# Sensors.net
KiCad netlist of a schematic drawn in EAGLE
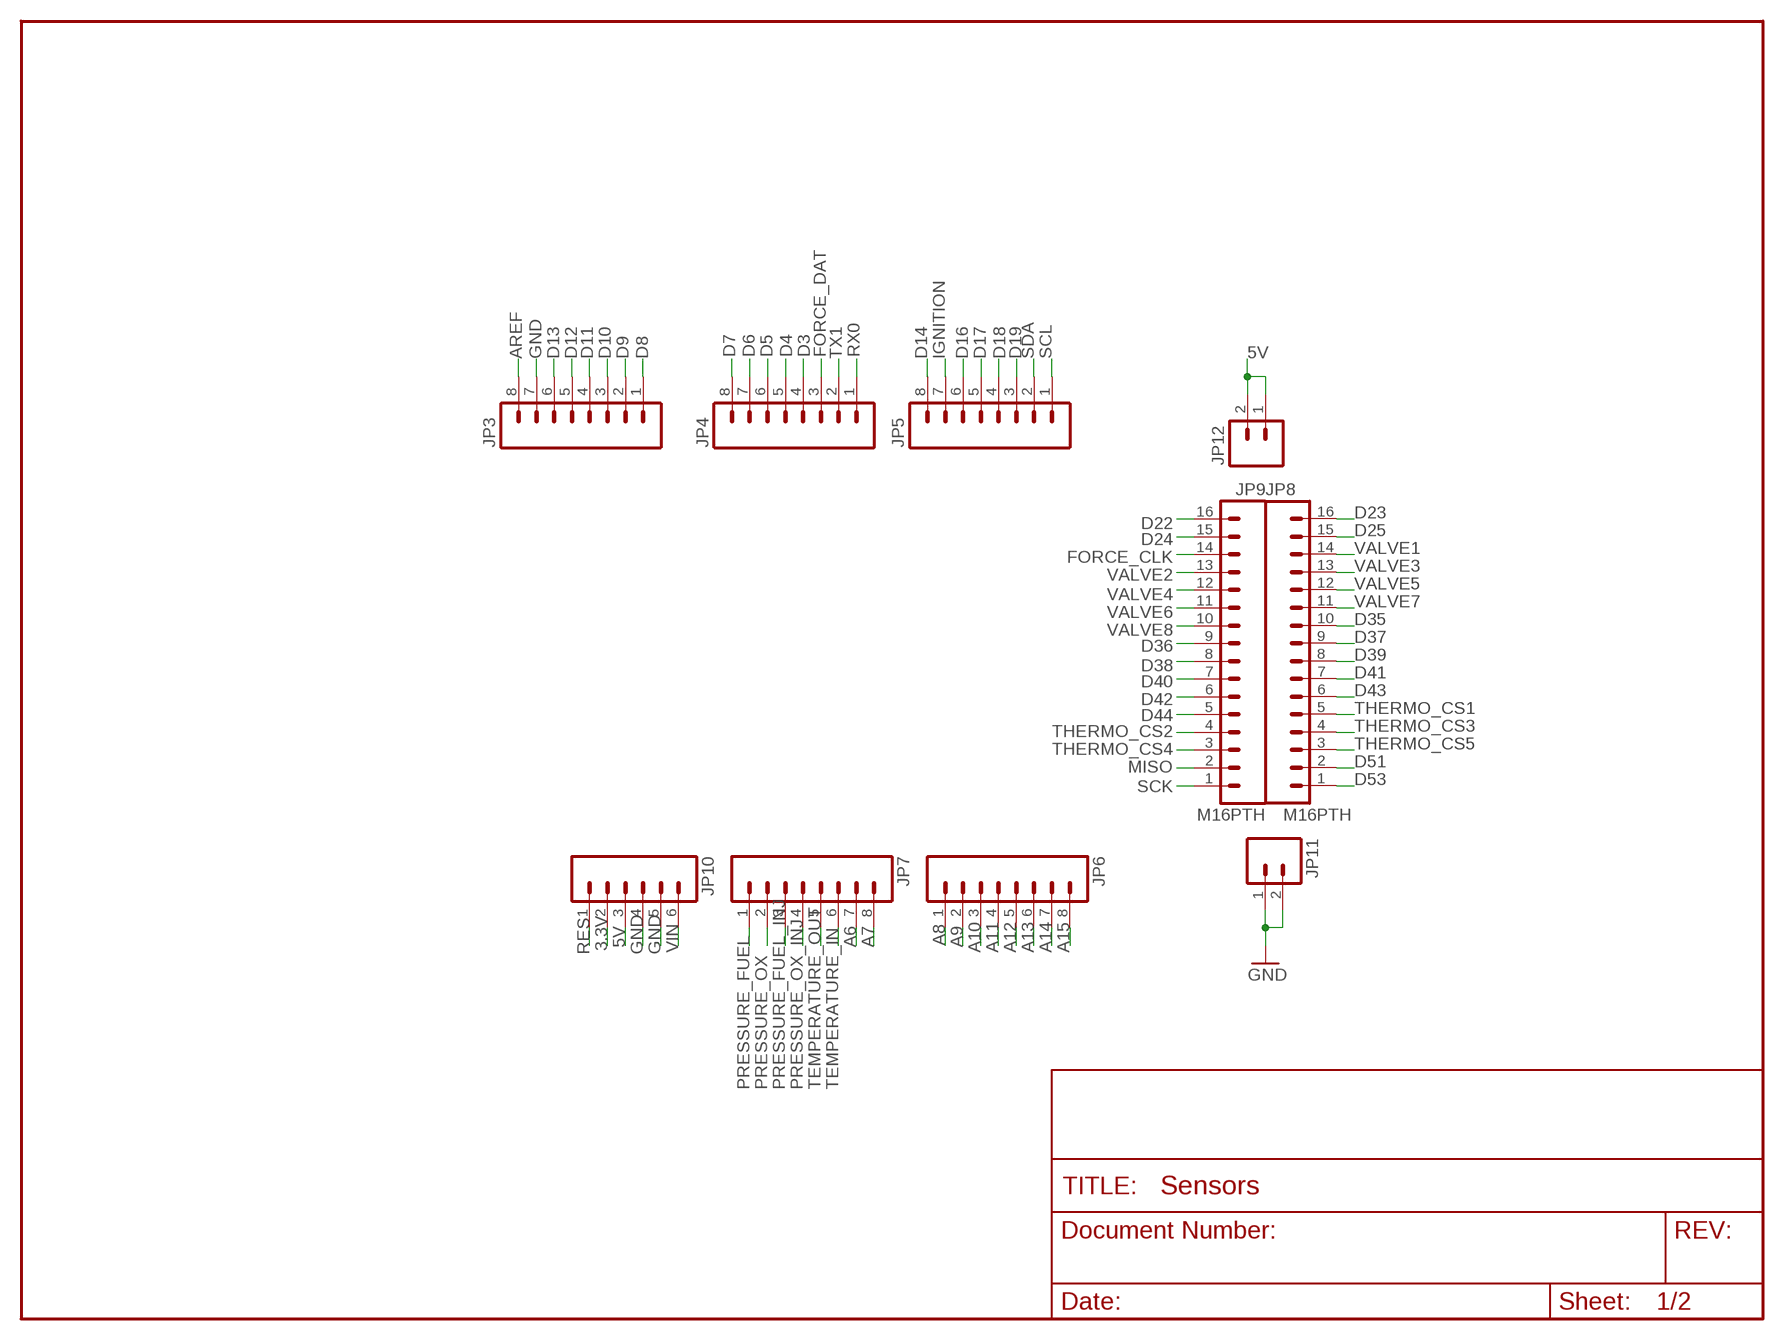
[diagram p0: schematic, sheet 1]
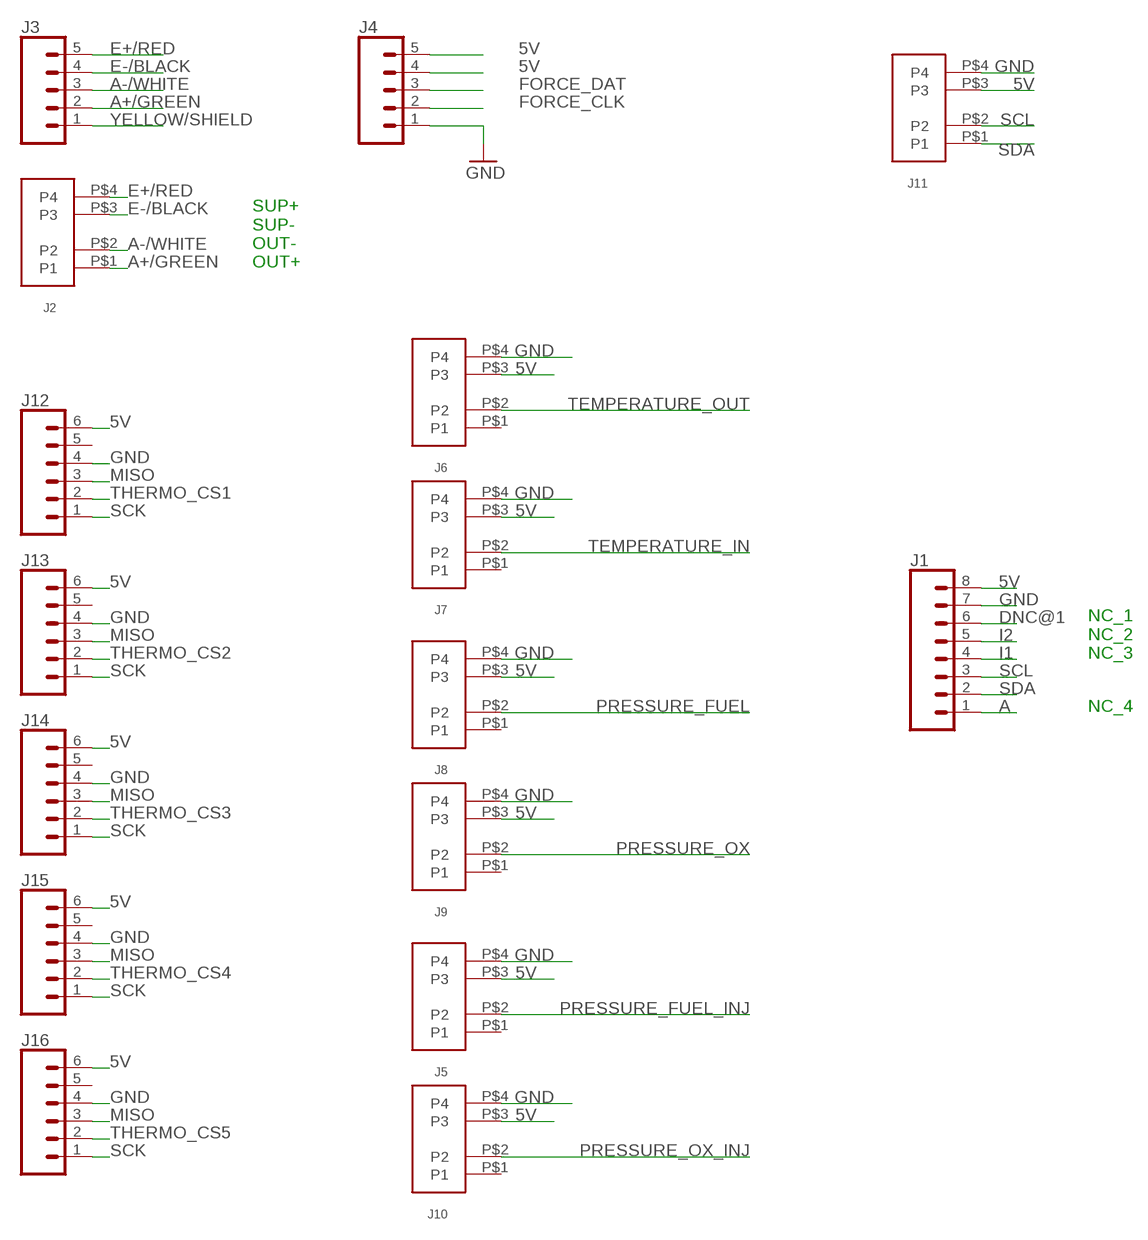
[diagram p1: schematic, sheet 2]

(export (version "E")
  (design (tool "Eeschema 10.0.6"))
  (components
    (comp (ref "J1")
      (value "CONN_08\"")
      (footprint "eagle-import:1X08")
      (libsource (lib "eagle-import") (part "CONN_08{dblquote}"))
    )
    (comp (ref "J2")
      (value "JST_CONNECTOR")
      (footprint "eagle-import:B4B-XH-A(LF)(SN)")
      (libsource (lib "eagle-import") (part "JST_CONNECTOR"))
    )
    (comp (ref "J3")
      (value "CONN_05")
      (footprint "eagle-import:1X05")
      (libsource (lib "eagle-import") (part "CONN_05"))
    )
    (comp (ref "J4")
      (value "CONN_05")
      (footprint "eagle-import:1X05")
      (libsource (lib "eagle-import") (part "CONN_05"))
    )
    (comp (ref "J5")
      (value "JST_CONNECTOR")
      (footprint "eagle-import:B4B-XH-A(LF)(SN)")
      (libsource (lib "eagle-import") (part "JST_CONNECTOR"))
    )
    (comp (ref "J6")
      (value "JST_CONNECTOR")
      (footprint "eagle-import:B4B-XH-A(LF)(SN)")
      (libsource (lib "eagle-import") (part "JST_CONNECTOR"))
    )
    (comp (ref "J7")
      (value "JST_CONNECTOR")
      (footprint "eagle-import:B4B-XH-A(LF)(SN)")
      (libsource (lib "eagle-import") (part "JST_CONNECTOR"))
    )
    (comp (ref "J8")
      (value "JST_CONNECTOR")
      (footprint "eagle-import:B4B-XH-A(LF)(SN)")
      (libsource (lib "eagle-import") (part "JST_CONNECTOR"))
    )
    (comp (ref "J9")
      (value "JST_CONNECTOR")
      (footprint "eagle-import:B4B-XH-A(LF)(SN)")
      (libsource (lib "eagle-import") (part "JST_CONNECTOR"))
    )
    (comp (ref "J10")
      (value "JST_CONNECTOR")
      (footprint "eagle-import:B4B-XH-A(LF)(SN)")
      (libsource (lib "eagle-import") (part "JST_CONNECTOR"))
    )
    (comp (ref "J11")
      (value "JST_CONNECTOR")
      (footprint "eagle-import:B4B-XH-A(LF)(SN)")
      (libsource (lib "eagle-import") (part "JST_CONNECTOR"))
    )
    (comp (ref "J12")
      (value "CONN_06SILK_FEMALE_PTH")
      (footprint "eagle-import:1X06")
      (libsource (lib "eagle-import") (part "CONN_06SILK_FEMALE_PTH"))
    )
    (comp (ref "J13")
      (value "CONN_06SILK_FEMALE_PTH")
      (footprint "eagle-import:1X06")
      (libsource (lib "eagle-import") (part "CONN_06SILK_FEMALE_PTH"))
    )
    (comp (ref "J14")
      (value "CONN_06SILK_FEMALE_PTH")
      (footprint "eagle-import:1X06")
      (libsource (lib "eagle-import") (part "CONN_06SILK_FEMALE_PTH"))
    )
    (comp (ref "J15")
      (value "CONN_06SILK_FEMALE_PTH")
      (footprint "eagle-import:1X06")
      (libsource (lib "eagle-import") (part "CONN_06SILK_FEMALE_PTH"))
    )
    (comp (ref "J16")
      (value "CONN_06SILK_FEMALE_PTH")
      (footprint "eagle-import:1X06")
      (libsource (lib "eagle-import") (part "CONN_06SILK_FEMALE_PTH"))
    )
    (comp (ref "JP3")
      (value "M08")
      (footprint "eagle-import:1X08")
      (libsource (lib "eagle-import") (part "M08"))
    )
    (comp (ref "JP4")
      (value "M08")
      (footprint "eagle-import:1X08")
      (libsource (lib "eagle-import") (part "M08"))
    )
    (comp (ref "JP5")
      (value "M08")
      (footprint "eagle-import:1X08")
      (libsource (lib "eagle-import") (part "M08"))
    )
    (comp (ref "JP6")
      (value "M08")
      (footprint "eagle-import:1X08")
      (libsource (lib "eagle-import") (part "M08"))
    )
    (comp (ref "JP7")
      (value "M08")
      (footprint "eagle-import:1X08")
      (libsource (lib "eagle-import") (part "M08"))
    )
    (comp (ref "JP8")
      (value "M16PTH")
      (footprint "eagle-import:1X16")
      (libsource (lib "eagle-import") (part "M16PTH"))
    )
    (comp (ref "JP9")
      (value "M16PTH")
      (footprint "eagle-import:1X16")
      (libsource (lib "eagle-import") (part "M16PTH"))
    )
    (comp (ref "JP10")
      (value "M06SIP")
      (footprint "eagle-import:1X06")
      (libsource (lib "eagle-import") (part "M06SIP"))
    )
    (comp (ref "JP11")
      (value "M02PTH")
      (footprint "eagle-import:1X02")
      (libsource (lib "eagle-import") (part "M02PTH"))
    )
    (comp (ref "JP12")
      (value "M02PTH")
      (footprint "eagle-import:1X02")
      (libsource (lib "eagle-import") (part "M02PTH"))
    )
  )
  (nets
    (net (code "1") (name "3.3V") (class "Default")
      (node (ref "JP10") (pin "2") (pinfunction "2_2") (pintype "passive"))
    )
    (net (code "2") (name "5V") (class "Default")
      (node (ref "J1") (pin "8") (pinfunction "8_8") (pintype "passive"))
      (node (ref "J10") (pin "P$3") (pinfunction "P3_P$3") (pintype "bidirectional"))
      (node (ref "J11") (pin "P$3") (pinfunction "P3_P$3") (pintype "bidirectional"))
      (node (ref "J12") (pin "6") (pinfunction "6_6") (pintype "passive"))
      (node (ref "J13") (pin "6") (pinfunction "6_6") (pintype "passive"))
      (node (ref "J14") (pin "6") (pinfunction "6_6") (pintype "passive"))
      (node (ref "J15") (pin "6") (pinfunction "6_6") (pintype "passive"))
      (node (ref "J16") (pin "6") (pinfunction "6_6") (pintype "passive"))
      (node (ref "J4") (pin "4") (pinfunction "4_4") (pintype "passive"))
      (node (ref "J4") (pin "5") (pinfunction "5_5") (pintype "passive"))
      (node (ref "J5") (pin "P$3") (pinfunction "P3_P$3") (pintype "bidirectional"))
      (node (ref "J6") (pin "P$3") (pinfunction "P3_P$3") (pintype "bidirectional"))
      (node (ref "J7") (pin "P$3") (pinfunction "P3_P$3") (pintype "bidirectional"))
      (node (ref "J8") (pin "P$3") (pinfunction "P3_P$3") (pintype "bidirectional"))
      (node (ref "J9") (pin "P$3") (pinfunction "P3_P$3") (pintype "bidirectional"))
      (node (ref "JP10") (pin "3") (pinfunction "3_3") (pintype "passive"))
      (node (ref "JP12") (pin "1") (pinfunction "1_1") (pintype "passive"))
      (node (ref "JP12") (pin "2") (pinfunction "2_2") (pintype "passive"))
    )
    (net (code "3") (name "A") (class "Default")
      (node (ref "J1") (pin "1") (pinfunction "1_1") (pintype "passive"))
    )
    (net (code "4") (name "A+{slash}GREEN") (class "Default")
      (node (ref "J2") (pin "P$1") (pinfunction "P1_P$1") (pintype "bidirectional"))
      (node (ref "J3") (pin "2") (pinfunction "2_2") (pintype "passive"))
    )
    (net (code "5") (name "A-{slash}WHITE") (class "Default")
      (node (ref "J2") (pin "P$2") (pinfunction "P2_P$2") (pintype "bidirectional"))
      (node (ref "J3") (pin "3") (pinfunction "3_3") (pintype "passive"))
    )
    (net (code "6") (name "A6") (class "Default")
      (node (ref "JP7") (pin "7") (pinfunction "7_7") (pintype "passive"))
    )
    (net (code "7") (name "A7") (class "Default")
      (node (ref "JP7") (pin "8") (pinfunction "8_8") (pintype "passive"))
    )
    (net (code "8") (name "A8") (class "Default")
      (node (ref "JP6") (pin "1") (pinfunction "1_1") (pintype "passive"))
    )
    (net (code "9") (name "A9") (class "Default")
      (node (ref "JP6") (pin "2") (pinfunction "2_2") (pintype "passive"))
    )
    (net (code "10") (name "A10") (class "Default")
      (node (ref "JP6") (pin "3") (pinfunction "3_3") (pintype "passive"))
    )
    (net (code "11") (name "A11") (class "Default")
      (node (ref "JP6") (pin "4") (pinfunction "4_4") (pintype "passive"))
    )
    (net (code "12") (name "A12") (class "Default")
      (node (ref "JP6") (pin "5") (pinfunction "5_5") (pintype "passive"))
    )
    (net (code "13") (name "A13") (class "Default")
      (node (ref "JP6") (pin "6") (pinfunction "6_6") (pintype "passive"))
    )
    (net (code "14") (name "A14") (class "Default")
      (node (ref "JP6") (pin "7") (pinfunction "7_7") (pintype "passive"))
    )
    (net (code "15") (name "A15") (class "Default")
      (node (ref "JP6") (pin "8") (pinfunction "8_8") (pintype "passive"))
    )
    (net (code "16") (name "AREF") (class "Default")
      (node (ref "JP3") (pin "8") (pinfunction "8_8") (pintype "passive"))
    )
    (net (code "17") (name "D3") (class "Default")
      (node (ref "JP4") (pin "4") (pinfunction "4_4") (pintype "passive"))
    )
    (net (code "18") (name "D4") (class "Default")
      (node (ref "JP4") (pin "5") (pinfunction "5_5") (pintype "passive"))
    )
    (net (code "19") (name "D5") (class "Default")
      (node (ref "JP4") (pin "6") (pinfunction "6_6") (pintype "passive"))
    )
    (net (code "20") (name "D6") (class "Default")
      (node (ref "JP4") (pin "7") (pinfunction "7_7") (pintype "passive"))
    )
    (net (code "21") (name "D7") (class "Default")
      (node (ref "JP4") (pin "8") (pinfunction "8_8") (pintype "passive"))
    )
    (net (code "22") (name "D8") (class "Default")
      (node (ref "JP3") (pin "1") (pinfunction "1_1") (pintype "passive"))
    )
    (net (code "23") (name "D9") (class "Default")
      (node (ref "JP3") (pin "2") (pinfunction "2_2") (pintype "passive"))
    )
    (net (code "24") (name "D10") (class "Default")
      (node (ref "JP3") (pin "3") (pinfunction "3_3") (pintype "passive"))
    )
    (net (code "25") (name "D11") (class "Default")
      (node (ref "JP3") (pin "4") (pinfunction "4_4") (pintype "passive"))
    )
    (net (code "26") (name "D12") (class "Default")
      (node (ref "JP3") (pin "5") (pinfunction "5_5") (pintype "passive"))
    )
    (net (code "27") (name "D13") (class "Default")
      (node (ref "JP3") (pin "6") (pinfunction "6_6") (pintype "passive"))
    )
    (net (code "28") (name "D14") (class "Default")
      (node (ref "JP5") (pin "8") (pinfunction "8_8") (pintype "passive"))
    )
    (net (code "29") (name "D16") (class "Default")
      (node (ref "JP5") (pin "6") (pinfunction "6_6") (pintype "passive"))
    )
    (net (code "30") (name "D17") (class "Default")
      (node (ref "JP5") (pin "5") (pinfunction "5_5") (pintype "passive"))
    )
    (net (code "31") (name "D18") (class "Default")
      (node (ref "JP5") (pin "4") (pinfunction "4_4") (pintype "passive"))
    )
    (net (code "32") (name "D19") (class "Default")
      (node (ref "JP5") (pin "3") (pinfunction "3_3") (pintype "passive"))
    )
    (net (code "33") (name "D22") (class "Default")
      (node (ref "JP9") (pin "16") (pinfunction "16_16") (pintype "passive"))
    )
    (net (code "34") (name "D23") (class "Default")
      (node (ref "JP8") (pin "16") (pinfunction "16_16") (pintype "passive"))
    )
    (net (code "35") (name "D24") (class "Default")
      (node (ref "JP9") (pin "15") (pinfunction "15_15") (pintype "passive"))
    )
    (net (code "36") (name "D25") (class "Default")
      (node (ref "JP8") (pin "15") (pinfunction "15_15") (pintype "passive"))
    )
    (net (code "37") (name "D35") (class "Default")
      (node (ref "JP8") (pin "10") (pinfunction "10_10") (pintype "passive"))
    )
    (net (code "38") (name "D36") (class "Default")
      (node (ref "JP9") (pin "9") (pinfunction "9_9") (pintype "passive"))
    )
    (net (code "39") (name "D37") (class "Default")
      (node (ref "JP8") (pin "9") (pinfunction "9_9") (pintype "passive"))
    )
    (net (code "40") (name "D38") (class "Default")
      (node (ref "JP9") (pin "8") (pinfunction "8_8") (pintype "passive"))
    )
    (net (code "41") (name "D39") (class "Default")
      (node (ref "JP8") (pin "8") (pinfunction "8_8") (pintype "passive"))
    )
    (net (code "42") (name "D40") (class "Default")
      (node (ref "JP9") (pin "7") (pinfunction "7_7") (pintype "passive"))
    )
    (net (code "43") (name "D41") (class "Default")
      (node (ref "JP8") (pin "7") (pinfunction "7_7") (pintype "passive"))
    )
    (net (code "44") (name "D42") (class "Default")
      (node (ref "JP9") (pin "6") (pinfunction "6_6") (pintype "passive"))
    )
    (net (code "45") (name "D43") (class "Default")
      (node (ref "JP8") (pin "6") (pinfunction "6_6") (pintype "passive"))
    )
    (net (code "46") (name "D44") (class "Default")
      (node (ref "JP9") (pin "5") (pinfunction "5_5") (pintype "passive"))
    )
    (net (code "47") (name "D51") (class "Default")
      (node (ref "JP8") (pin "2") (pinfunction "2_2") (pintype "passive"))
    )
    (net (code "48") (name "D53") (class "Default")
      (node (ref "JP8") (pin "1") (pinfunction "1_1") (pintype "passive"))
    )
    (net (code "49") (name "DNC@1") (class "Default")
      (node (ref "J1") (pin "6") (pinfunction "6_6") (pintype "passive"))
    )
    (net (code "50") (name "E+{slash}RED") (class "Default")
      (node (ref "J2") (pin "P$4") (pinfunction "P4_P$4") (pintype "bidirectional"))
      (node (ref "J3") (pin "5") (pinfunction "5_5") (pintype "passive"))
    )
    (net (code "51") (name "E-{slash}BLACK") (class "Default")
      (node (ref "J2") (pin "P$3") (pinfunction "P3_P$3") (pintype "bidirectional"))
      (node (ref "J3") (pin "4") (pinfunction "4_4") (pintype "passive"))
    )
    (net (code "52") (name "FORCE_CLK") (class "Default")
      (node (ref "J4") (pin "2") (pinfunction "2_2") (pintype "passive"))
      (node (ref "JP9") (pin "14") (pinfunction "14_14") (pintype "passive"))
    )
    (net (code "53") (name "FORCE_DAT") (class "Default")
      (node (ref "J4") (pin "3") (pinfunction "3_3") (pintype "passive"))
      (node (ref "JP4") (pin "3") (pinfunction "3_3") (pintype "passive"))
    )
    (net (code "54") (name "GND") (class "Default")
      (node (ref "J1") (pin "7") (pinfunction "7_7") (pintype "passive"))
      (node (ref "J10") (pin "P$4") (pinfunction "P4_P$4") (pintype "bidirectional"))
      (node (ref "J11") (pin "P$4") (pinfunction "P4_P$4") (pintype "bidirectional"))
      (node (ref "J12") (pin "4") (pinfunction "4_4") (pintype "passive"))
      (node (ref "J13") (pin "4") (pinfunction "4_4") (pintype "passive"))
      (node (ref "J14") (pin "4") (pinfunction "4_4") (pintype "passive"))
      (node (ref "J15") (pin "4") (pinfunction "4_4") (pintype "passive"))
      (node (ref "J16") (pin "4") (pinfunction "4_4") (pintype "passive"))
      (node (ref "J4") (pin "1") (pinfunction "1_1") (pintype "passive"))
      (node (ref "J5") (pin "P$4") (pinfunction "P4_P$4") (pintype "bidirectional"))
      (node (ref "J6") (pin "P$4") (pinfunction "P4_P$4") (pintype "bidirectional"))
      (node (ref "J7") (pin "P$4") (pinfunction "P4_P$4") (pintype "bidirectional"))
      (node (ref "J8") (pin "P$4") (pinfunction "P4_P$4") (pintype "bidirectional"))
      (node (ref "J9") (pin "P$4") (pinfunction "P4_P$4") (pintype "bidirectional"))
      (node (ref "JP10") (pin "4") (pinfunction "4_4") (pintype "passive"))
      (node (ref "JP10") (pin "5") (pinfunction "5_5") (pintype "passive"))
      (node (ref "JP11") (pin "1") (pinfunction "1_1") (pintype "passive"))
      (node (ref "JP11") (pin "2") (pinfunction "2_2") (pintype "passive"))
      (node (ref "JP3") (pin "7") (pinfunction "7_7") (pintype "passive"))
    )
    (net (code "55") (name "I1") (class "Default")
      (node (ref "J1") (pin "4") (pinfunction "4_4") (pintype "passive"))
    )
    (net (code "56") (name "I2") (class "Default")
      (node (ref "J1") (pin "5") (pinfunction "5_5") (pintype "passive"))
    )
    (net (code "57") (name "IGNITION") (class "Default")
      (node (ref "JP5") (pin "7") (pinfunction "7_7") (pintype "passive"))
    )
    (net (code "58") (name "MISO") (class "Default")
      (node (ref "J12") (pin "3") (pinfunction "3_3") (pintype "passive"))
      (node (ref "J13") (pin "3") (pinfunction "3_3") (pintype "passive"))
      (node (ref "J14") (pin "3") (pinfunction "3_3") (pintype "passive"))
      (node (ref "J15") (pin "3") (pinfunction "3_3") (pintype "passive"))
      (node (ref "J16") (pin "3") (pinfunction "3_3") (pintype "passive"))
      (node (ref "JP9") (pin "2") (pinfunction "2_2") (pintype "passive"))
    )
    (net (code "59") (name "PRESSURE_FUEL") (class "Default")
      (node (ref "J8") (pin "P$2") (pinfunction "P2_P$2") (pintype "bidirectional"))
      (node (ref "JP7") (pin "1") (pinfunction "1_1") (pintype "passive"))
    )
    (net (code "60") (name "PRESSURE_FUEL_INJ") (class "Default")
      (node (ref "J5") (pin "P$2") (pinfunction "P2_P$2") (pintype "bidirectional"))
      (node (ref "JP7") (pin "3") (pinfunction "3_3") (pintype "passive"))
    )
    (net (code "61") (name "PRESSURE_OX") (class "Default")
      (node (ref "J9") (pin "P$2") (pinfunction "P2_P$2") (pintype "bidirectional"))
      (node (ref "JP7") (pin "2") (pinfunction "2_2") (pintype "passive"))
    )
    (net (code "62") (name "PRESSURE_OX_INJ") (class "Default")
      (node (ref "J10") (pin "P$2") (pinfunction "P2_P$2") (pintype "bidirectional"))
      (node (ref "JP7") (pin "4") (pinfunction "4_4") (pintype "passive"))
    )
    (net (code "63") (name "RES") (class "Default")
      (node (ref "JP10") (pin "1") (pinfunction "1_1") (pintype "passive"))
    )
    (net (code "64") (name "RX0") (class "Default")
      (node (ref "JP4") (pin "1") (pinfunction "1_1") (pintype "passive"))
    )
    (net (code "65") (name "SCK") (class "Default")
      (node (ref "J12") (pin "1") (pinfunction "1_1") (pintype "passive"))
      (node (ref "J13") (pin "1") (pinfunction "1_1") (pintype "passive"))
      (node (ref "J14") (pin "1") (pinfunction "1_1") (pintype "passive"))
      (node (ref "J15") (pin "1") (pinfunction "1_1") (pintype "passive"))
      (node (ref "J16") (pin "1") (pinfunction "1_1") (pintype "passive"))
      (node (ref "JP9") (pin "1") (pinfunction "1_1") (pintype "passive"))
    )
    (net (code "66") (name "SCL") (class "Default")
      (node (ref "J1") (pin "3") (pinfunction "3_3") (pintype "passive"))
      (node (ref "J11") (pin "P$2") (pinfunction "P2_P$2") (pintype "bidirectional"))
      (node (ref "JP5") (pin "1") (pinfunction "1_1") (pintype "passive"))
    )
    (net (code "67") (name "SDA") (class "Default")
      (node (ref "J1") (pin "2") (pinfunction "2_2") (pintype "passive"))
      (node (ref "J11") (pin "P$1") (pinfunction "P1_P$1") (pintype "bidirectional"))
      (node (ref "JP5") (pin "2") (pinfunction "2_2") (pintype "passive"))
    )
    (net (code "68") (name "TEMPERATURE_IN") (class "Default")
      (node (ref "J7") (pin "P$2") (pinfunction "P2_P$2") (pintype "bidirectional"))
      (node (ref "JP7") (pin "6") (pinfunction "6_6") (pintype "passive"))
    )
    (net (code "69") (name "TEMPERATURE_OUT") (class "Default")
      (node (ref "J6") (pin "P$2") (pinfunction "P2_P$2") (pintype "bidirectional"))
      (node (ref "JP7") (pin "5") (pinfunction "5_5") (pintype "passive"))
    )
    (net (code "70") (name "THERMO_CS1") (class "Default")
      (node (ref "J12") (pin "2") (pinfunction "2_2") (pintype "passive"))
      (node (ref "JP8") (pin "5") (pinfunction "5_5") (pintype "passive"))
    )
    (net (code "71") (name "THERMO_CS2") (class "Default")
      (node (ref "J13") (pin "2") (pinfunction "2_2") (pintype "passive"))
      (node (ref "JP9") (pin "4") (pinfunction "4_4") (pintype "passive"))
    )
    (net (code "72") (name "THERMO_CS3") (class "Default")
      (node (ref "J14") (pin "2") (pinfunction "2_2") (pintype "passive"))
      (node (ref "JP8") (pin "4") (pinfunction "4_4") (pintype "passive"))
    )
    (net (code "73") (name "THERMO_CS4") (class "Default")
      (node (ref "J15") (pin "2") (pinfunction "2_2") (pintype "passive"))
      (node (ref "JP9") (pin "3") (pinfunction "3_3") (pintype "passive"))
    )
    (net (code "74") (name "THERMO_CS5") (class "Default")
      (node (ref "J16") (pin "2") (pinfunction "2_2") (pintype "passive"))
      (node (ref "JP8") (pin "3") (pinfunction "3_3") (pintype "passive"))
    )
    (net (code "75") (name "TX1") (class "Default")
      (node (ref "JP4") (pin "2") (pinfunction "2_2") (pintype "passive"))
    )
    (net (code "76") (name "VALVE1") (class "Default")
      (node (ref "JP8") (pin "14") (pinfunction "14_14") (pintype "passive"))
    )
    (net (code "77") (name "VALVE2") (class "Default")
      (node (ref "JP9") (pin "13") (pinfunction "13_13") (pintype "passive"))
    )
    (net (code "78") (name "VALVE3") (class "Default")
      (node (ref "JP8") (pin "13") (pinfunction "13_13") (pintype "passive"))
    )
    (net (code "79") (name "VALVE4") (class "Default")
      (node (ref "JP9") (pin "12") (pinfunction "12_12") (pintype "passive"))
    )
    (net (code "80") (name "VALVE5") (class "Default")
      (node (ref "JP8") (pin "12") (pinfunction "12_12") (pintype "passive"))
    )
    (net (code "81") (name "VALVE6") (class "Default")
      (node (ref "JP9") (pin "11") (pinfunction "11_11") (pintype "passive"))
    )
    (net (code "82") (name "VALVE7") (class "Default")
      (node (ref "JP8") (pin "11") (pinfunction "11_11") (pintype "passive"))
    )
    (net (code "83") (name "VALVE8") (class "Default")
      (node (ref "JP9") (pin "10") (pinfunction "10_10") (pintype "passive"))
    )
    (net (code "84") (name "VIN") (class "Default")
      (node (ref "JP10") (pin "6") (pinfunction "6_6") (pintype "passive"))
    )
    (net (code "85") (name "YELLOW{slash}SHIELD") (class "Default")
      (node (ref "J3") (pin "1") (pinfunction "1_1") (pintype "passive"))
    )
    (net (code "86") (name "unconnected-(J5-P1-PadP$1)") (class "Default")
      (node (ref "J5") (pin "P$1") (pinfunction "P1_P$1") (pintype "bidirectional"))
    )
    (net (code "87") (name "unconnected-(J6-P1-PadP$1)") (class "Default")
      (node (ref "J6") (pin "P$1") (pinfunction "P1_P$1") (pintype "bidirectional"))
    )
    (net (code "88") (name "unconnected-(J7-P1-PadP$1)") (class "Default")
      (node (ref "J7") (pin "P$1") (pinfunction "P1_P$1") (pintype "bidirectional"))
    )
    (net (code "89") (name "unconnected-(J8-P1-PadP$1)") (class "Default")
      (node (ref "J8") (pin "P$1") (pinfunction "P1_P$1") (pintype "bidirectional"))
    )
    (net (code "90") (name "unconnected-(J9-P1-PadP$1)") (class "Default")
      (node (ref "J9") (pin "P$1") (pinfunction "P1_P$1") (pintype "bidirectional"))
    )
    (net (code "91") (name "unconnected-(J10-P1-PadP$1)") (class "Default")
      (node (ref "J10") (pin "P$1") (pinfunction "P1_P$1") (pintype "bidirectional"))
    )
    (net (code "92") (name "unconnected-(J12-Pad5)") (class "Default")
      (node (ref "J12") (pin "5") (pinfunction "5_5") (pintype "passive"))
    )
    (net (code "93") (name "unconnected-(J13-Pad5)") (class "Default")
      (node (ref "J13") (pin "5") (pinfunction "5_5") (pintype "passive"))
    )
    (net (code "94") (name "unconnected-(J14-Pad5)") (class "Default")
      (node (ref "J14") (pin "5") (pinfunction "5_5") (pintype "passive"))
    )
    (net (code "95") (name "unconnected-(J15-Pad5)") (class "Default")
      (node (ref "J15") (pin "5") (pinfunction "5_5") (pintype "passive"))
    )
    (net (code "96") (name "unconnected-(J16-Pad5)") (class "Default")
      (node (ref "J16") (pin "5") (pinfunction "5_5") (pintype "passive"))
    )
  )
)
